# esp32_master_board.net
KiCad netlist of a schematic drawn in EAGLE
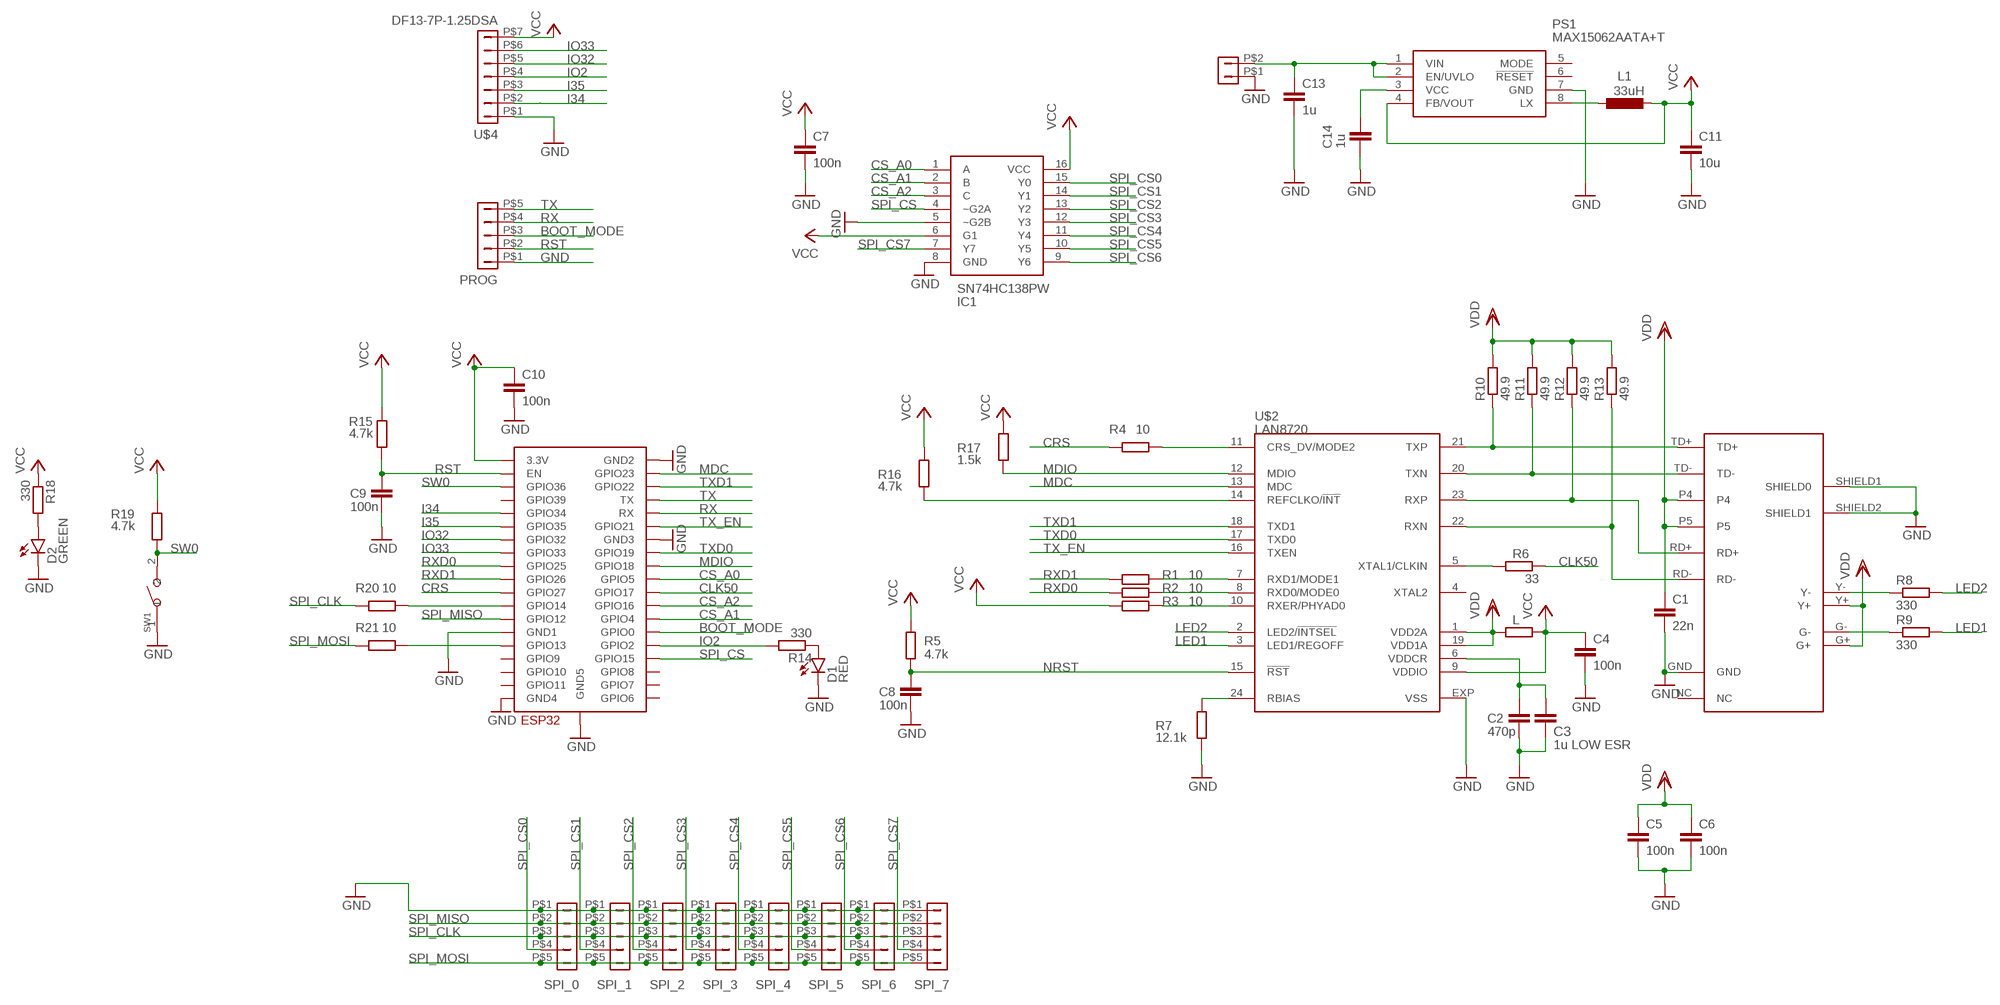
[diagram p0: schematic, sheet 1]

(export (version "E")
  (design (tool "Eeschema 10.0.6"))
  (components
    (comp (ref "C1")
      (value "22n")
      (footprint "eagle-import:C0402")
      (libsource (lib "eagle-import") (part "C-EUC0402"))
    )
    (comp (ref "C2")
      (value "470p")
      (footprint "eagle-import:C0402")
      (libsource (lib "eagle-import") (part "C-EUC0402"))
    )
    (comp (ref "C3")
      (value "1u LOW ESR")
      (footprint "eagle-import:C0402")
      (libsource (lib "eagle-import") (part "C-EUC0402"))
    )
    (comp (ref "C4")
      (value "100n")
      (footprint "eagle-import:C0402")
      (libsource (lib "eagle-import") (part "C-EUC0402"))
    )
    (comp (ref "C5")
      (value "100n")
      (footprint "eagle-import:C0402")
      (libsource (lib "eagle-import") (part "C-EUC0402"))
    )
    (comp (ref "C6")
      (value "100n")
      (footprint "eagle-import:C0402")
      (libsource (lib "eagle-import") (part "C-EUC0402"))
    )
    (comp (ref "C7")
      (value "100n")
      (footprint "eagle-import:C0402")
      (libsource (lib "eagle-import") (part "C-EUC0402"))
    )
    (comp (ref "C8")
      (value "100n")
      (footprint "eagle-import:C0402")
      (libsource (lib "eagle-import") (part "C-EUC0402"))
    )
    (comp (ref "C9")
      (value "100n")
      (footprint "eagle-import:C0402")
      (libsource (lib "eagle-import") (part "C-EUC0402"))
    )
    (comp (ref "C10")
      (value "100n")
      (footprint "eagle-import:C0805K")
      (libsource (lib "eagle-import") (part "C-EUC0805K"))
    )
    (comp (ref "C11")
      (value "10u")
      (footprint "eagle-import:C0805K")
      (libsource (lib "eagle-import") (part "C-EUC0805K"))
    )
    (comp (ref "C13")
      (value "1u")
      (footprint "eagle-import:C0805K")
      (libsource (lib "eagle-import") (part "C-EUC0805K"))
    )
    (comp (ref "C14")
      (value "1u")
      (footprint "eagle-import:C0402")
      (libsource (lib "eagle-import") (part "C-EUC0402"))
    )
    (comp (ref "D1")
      (value "RED")
      (footprint "eagle-import:CHIPLED_0805")
      (libsource (lib "eagle-import") (part "LEDCHIPLED_0805"))
    )
    (comp (ref "D2")
      (value "GREEN")
      (footprint "eagle-import:CHIPLED_0805")
      (libsource (lib "eagle-import") (part "LEDCHIPLED_0805"))
    )
    (comp (ref "IC1")
      (value "SN74HC138PW")
      (footprint "eagle-import:SOP65P640X120-16N")
      (fields (field (name "RS_PART_NUMBER") "6631928"))
      (libsource (lib "eagle-import") (part "SN74HC138PW"))
    )
    (comp (ref "L")
      (value "R-EU_R0402")
      (footprint "eagle-import:R0402")
      (libsource (lib "eagle-import") (part "R-EU_R0402"))
    )
    (comp (ref "L1")
      (value "33uH")
      (footprint "eagle-import:POWER-CHOKE_WE-TPC")
      (libsource (lib "eagle-import") (part "L-EUWE-TPC"))
    )
    (comp (ref "POWER")
      (value "DF13-2P-1.25DSA")
      (footprint "eagle-import:DF13-2P-1.25DSA")
      (libsource (lib "eagle-import") (part "DF13-2P-1.25DSA"))
    )
    (comp (ref "PROG")
      (value "DF13-5P-1.25DSA")
      (footprint "eagle-import:DF13-5P-1.25DSA")
      (libsource (lib "eagle-import") (part "DF13-5P-1.25DSA"))
    )
    (comp (ref "PS1")
      (value "MAX15062AATA+T")
      (footprint "eagle-import:MAX14591ETAT")
      (fields (field (name "MOUSER_PART_NUMBER") "700-MAX15062AATA+T"))
      (libsource (lib "eagle-import") (part "MAX15062AATA+T"))
    )
    (comp (ref "R1")
      (value "10")
      (footprint "eagle-import:R0402")
      (libsource (lib "eagle-import") (part "R-EU_R0402"))
    )
    (comp (ref "R2")
      (value "10")
      (footprint "eagle-import:R0402")
      (libsource (lib "eagle-import") (part "R-EU_R0402"))
    )
    (comp (ref "R3")
      (value "10")
      (footprint "eagle-import:R0402")
      (libsource (lib "eagle-import") (part "R-EU_R0402"))
    )
    (comp (ref "R4")
      (value "10")
      (footprint "eagle-import:R0402")
      (libsource (lib "eagle-import") (part "R-EU_R0402"))
    )
    (comp (ref "R5")
      (value "4.7k")
      (footprint "eagle-import:R0402")
      (libsource (lib "eagle-import") (part "R-EU_R0402"))
    )
    (comp (ref "R6")
      (value "33")
      (footprint "eagle-import:R0402")
      (libsource (lib "eagle-import") (part "R-EU_R0402"))
    )
    (comp (ref "R7")
      (value "12.1k")
      (footprint "eagle-import:R0402")
      (libsource (lib "eagle-import") (part "R-EU_R0402"))
    )
    (comp (ref "R8")
      (value "330")
      (footprint "eagle-import:R0402")
      (libsource (lib "eagle-import") (part "R-EU_R0402"))
    )
    (comp (ref "R9")
      (value "330")
      (footprint "eagle-import:R0402")
      (libsource (lib "eagle-import") (part "R-EU_R0402"))
    )
    (comp (ref "R10")
      (value "49.9")
      (footprint "eagle-import:R0402")
      (libsource (lib "eagle-import") (part "R-EU_R0402"))
    )
    (comp (ref "R11")
      (value "49.9")
      (footprint "eagle-import:R0402")
      (libsource (lib "eagle-import") (part "R-EU_R0402"))
    )
    (comp (ref "R12")
      (value "49.9")
      (footprint "eagle-import:R0402")
      (libsource (lib "eagle-import") (part "R-EU_R0402"))
    )
    (comp (ref "R13")
      (value "49.9")
      (footprint "eagle-import:R0402")
      (libsource (lib "eagle-import") (part "R-EU_R0402"))
    )
    (comp (ref "R14")
      (value "330")
      (footprint "eagle-import:R0402")
      (libsource (lib "eagle-import") (part "R-EU_R0402"))
    )
    (comp (ref "R15")
      (value "4.7k")
      (footprint "eagle-import:R0402")
      (libsource (lib "eagle-import") (part "R-EU_R0402"))
    )
    (comp (ref "R16")
      (value "4.7k")
      (footprint "eagle-import:R0402")
      (libsource (lib "eagle-import") (part "R-EU_R0402"))
    )
    (comp (ref "R17")
      (value "1.5k")
      (footprint "eagle-import:R0402")
      (libsource (lib "eagle-import") (part "R-EU_R0402"))
    )
    (comp (ref "R18")
      (value "330")
      (footprint "eagle-import:R0402")
      (libsource (lib "eagle-import") (part "R-EU_R0402"))
    )
    (comp (ref "R19")
      (value "4.7k")
      (footprint "eagle-import:R0402")
      (libsource (lib "eagle-import") (part "R-EU_R0402"))
    )
    (comp (ref "R20")
      (value "10")
      (footprint "eagle-import:R0402")
      (libsource (lib "eagle-import") (part "R-EU_R0402"))
    )
    (comp (ref "R21")
      (value "10")
      (footprint "eagle-import:R0402")
      (libsource (lib "eagle-import") (part "R-EU_R0402"))
    )
    (comp (ref "SPI_0")
      (value "DF13-5P-1.25DSA")
      (footprint "eagle-import:DF13-5P-1.25DSA")
      (libsource (lib "eagle-import") (part "DF13-5P-1.25DSA"))
    )
    (comp (ref "SPI_1")
      (value "DF13-5P-1.25DSA")
      (footprint "eagle-import:DF13-5P-1.25DSA")
      (libsource (lib "eagle-import") (part "DF13-5P-1.25DSA"))
    )
    (comp (ref "SPI_2")
      (value "DF13-5P-1.25DSA")
      (footprint "eagle-import:DF13-5P-1.25DSA")
      (libsource (lib "eagle-import") (part "DF13-5P-1.25DSA"))
    )
    (comp (ref "SPI_3")
      (value "DF13-5P-1.25DSA")
      (footprint "eagle-import:DF13-5P-1.25DSA")
      (libsource (lib "eagle-import") (part "DF13-5P-1.25DSA"))
    )
    (comp (ref "SPI_4")
      (value "DF13-5P-1.25DSA")
      (footprint "eagle-import:DF13-5P-1.25DSA")
      (libsource (lib "eagle-import") (part "DF13-5P-1.25DSA"))
    )
    (comp (ref "SPI_5")
      (value "DF13-5P-1.25DSA")
      (footprint "eagle-import:DF13-5P-1.25DSA")
      (libsource (lib "eagle-import") (part "DF13-5P-1.25DSA"))
    )
    (comp (ref "SPI_6")
      (value "DF13-5P-1.25DSA")
      (footprint "eagle-import:DF13-5P-1.25DSA")
      (libsource (lib "eagle-import") (part "DF13-5P-1.25DSA"))
    )
    (comp (ref "SPI_7")
      (value "DF13-5P-1.25DSA")
      (footprint "eagle-import:DF13-5P-1.25DSA")
      (libsource (lib "eagle-import") (part "DF13-5P-1.25DSA"))
    )
    (comp (ref "SW1")
      (value "B3U-1000P-2P-SMD")
      (footprint "eagle-import:SW2-2.6-3.0X2.5X1.2+0.4MM")
      (libsource (lib "eagle-import") (part "SMD-BUTTON(2P-3.0X2.5X1.2+0.4MM)-B3U-1000P-2P-SMD"))
    )
    (comp (ref "U$1")
      (value "ESP32-WROOM")
      (footprint "eagle-import:ESP32-WROOM")
      (libsource (lib "eagle-import") (part "ESP32-WROOM"))
    )
    (comp (ref "U$2")
      (value "LAN8720")
      (footprint "eagle-import:QFN24")
      (libsource (lib "eagle-import") (part "LAN8720"))
    )
    (comp (ref "U$3")
      (value "HR911105A")
      (footprint "eagle-import:RJ45")
      (libsource (lib "eagle-import") (part "HR911105A"))
    )
    (comp (ref "U$4")
      (value "DF13-7P-1.25DSA")
      (footprint "eagle-import:DF13-7P-1.25DSA")
      (libsource (lib "eagle-import") (part "DF13-7P-1.25DSA"))
    )
  )
  (nets
    (net (code "1") (name "/BOOT_MODE") (class "Default")
      (node (ref "PROG") (pin "P$3") (pinfunction "3_P$3") (pintype "passive"))
      (node (ref "U$1") (pin "IO0") (pinfunction "GPIO0_IO0") (pintype "bidirectional"))
    )
    (net (code "2") (name "/CLK50") (class "Default")
      (node (ref "R6") (pin "1") (pinfunction "1_1") (pintype "passive"))
      (node (ref "U$1") (pin "IO17") (pinfunction "GPIO17_IO17") (pintype "bidirectional"))
    )
    (net (code "3") (name "/CRS") (class "Default")
      (node (ref "R4") (pin "1") (pinfunction "1_1") (pintype "passive"))
      (node (ref "U$1") (pin "IO27") (pinfunction "GPIO27_IO27") (pintype "bidirectional"))
    )
    (net (code "4") (name "/CS_A0") (class "Default")
      (node (ref "IC1") (pin "1") (pinfunction "A_1") (pintype "bidirectional"))
      (node (ref "U$1") (pin "IO5") (pinfunction "GPIO5_IO5") (pintype "bidirectional"))
    )
    (net (code "5") (name "/CS_A1") (class "Default")
      (node (ref "IC1") (pin "2") (pinfunction "B_2") (pintype "bidirectional"))
      (node (ref "U$1") (pin "IO4") (pinfunction "GPIO4_IO4") (pintype "bidirectional"))
    )
    (net (code "6") (name "/CS_A2") (class "Default")
      (node (ref "IC1") (pin "3") (pinfunction "C_3") (pintype "bidirectional"))
      (node (ref "U$1") (pin "IO16") (pinfunction "GPIO16_IO16") (pintype "bidirectional"))
    )
    (net (code "7") (name "/I34") (class "Default")
      (node (ref "U$1") (pin "IO34") (pinfunction "GPIO34_IO34") (pintype "bidirectional"))
      (node (ref "U$4") (pin "P$2") (pinfunction "2_P$2") (pintype "passive"))
    )
    (net (code "8") (name "/I35") (class "Default")
      (node (ref "U$1") (pin "IO35") (pinfunction "GPIO35_IO35") (pintype "bidirectional"))
      (node (ref "U$4") (pin "P$3") (pinfunction "3_P$3") (pintype "passive"))
    )
    (net (code "9") (name "/IO2") (class "Default")
      (node (ref "R14") (pin "2") (pinfunction "2_2") (pintype "passive"))
      (node (ref "U$1") (pin "IO2") (pinfunction "GPIO2_IO2") (pintype "bidirectional"))
      (node (ref "U$4") (pin "P$4") (pinfunction "4_P$4") (pintype "passive"))
    )
    (net (code "10") (name "/IO32") (class "Default")
      (node (ref "U$1") (pin "IO32") (pinfunction "GPIO32_IO32") (pintype "bidirectional"))
      (node (ref "U$4") (pin "P$5") (pinfunction "5_P$5") (pintype "passive"))
    )
    (net (code "11") (name "/IO33") (class "Default")
      (node (ref "U$1") (pin "IO33") (pinfunction "GPIO33_IO33") (pintype "bidirectional"))
      (node (ref "U$4") (pin "P$6") (pinfunction "6_P$6") (pintype "passive"))
    )
    (net (code "12") (name "/LED1") (class "Default")
      (node (ref "R9") (pin "2") (pinfunction "2_2") (pintype "passive"))
      (node (ref "U$2") (pin "3") (pinfunction "LED1/REGOFF_3") (pintype "bidirectional"))
    )
    (net (code "13") (name "/LED2") (class "Default")
      (node (ref "R8") (pin "2") (pinfunction "2_2") (pintype "passive"))
      (node (ref "U$2") (pin "2") (pinfunction "LED2/~{INTSEL}_2") (pintype "bidirectional"))
    )
    (net (code "14") (name "/MDC") (class "Default")
      (node (ref "U$1") (pin "IO23") (pinfunction "GPIO23_IO23") (pintype "bidirectional"))
      (node (ref "U$2") (pin "13") (pinfunction "MDC_13") (pintype "bidirectional"))
    )
    (net (code "15") (name "/MDIO") (class "Default")
      (node (ref "R17") (pin "1") (pinfunction "1_1") (pintype "passive"))
      (node (ref "U$1") (pin "IO18") (pinfunction "GPIO18_IO18") (pintype "bidirectional"))
      (node (ref "U$2") (pin "12") (pinfunction "MDIO_12") (pintype "bidirectional"))
    )
    (net (code "16") (name "/NRST") (class "Default")
      (node (ref "C8") (pin "1") (pinfunction "1_1") (pintype "passive"))
      (node (ref "R5") (pin "1") (pinfunction "1_1") (pintype "passive"))
      (node (ref "U$2") (pin "15") (pinfunction "~{RST}_15") (pintype "bidirectional"))
    )
    (net (code "17") (name "/RST") (class "Default")
      (node (ref "C9") (pin "1") (pinfunction "1_1") (pintype "passive"))
      (node (ref "PROG") (pin "P$2") (pinfunction "2_P$2") (pintype "passive"))
      (node (ref "R15") (pin "1") (pinfunction "1_1") (pintype "passive"))
      (node (ref "U$1") (pin "EN") (pinfunction "EN_EN") (pintype "bidirectional"))
    )
    (net (code "18") (name "/RX") (class "Default")
      (node (ref "PROG") (pin "P$4") (pinfunction "4_P$4") (pintype "passive"))
      (node (ref "U$1") (pin "RX") (pinfunction "RX_RX") (pintype "bidirectional"))
    )
    (net (code "19") (name "/RXD0") (class "Default")
      (node (ref "R2") (pin "1") (pinfunction "1_1") (pintype "passive"))
      (node (ref "U$1") (pin "IO25") (pinfunction "GPIO25_IO25") (pintype "bidirectional"))
    )
    (net (code "20") (name "/RXD1") (class "Default")
      (node (ref "R1") (pin "1") (pinfunction "1_1") (pintype "passive"))
      (node (ref "U$1") (pin "IO26") (pinfunction "GPIO26_IO26") (pintype "bidirectional"))
    )
    (net (code "21") (name "/SPI_CLK") (class "Default")
      (node (ref "R20") (pin "1") (pinfunction "1_1") (pintype "passive"))
      (node (ref "SPI_0") (pin "P$3") (pinfunction "3_P$3") (pintype "passive"))
      (node (ref "SPI_1") (pin "P$3") (pinfunction "3_P$3") (pintype "passive"))
      (node (ref "SPI_2") (pin "P$3") (pinfunction "3_P$3") (pintype "passive"))
      (node (ref "SPI_3") (pin "P$3") (pinfunction "3_P$3") (pintype "passive"))
      (node (ref "SPI_4") (pin "P$3") (pinfunction "3_P$3") (pintype "passive"))
      (node (ref "SPI_5") (pin "P$3") (pinfunction "3_P$3") (pintype "passive"))
      (node (ref "SPI_6") (pin "P$3") (pinfunction "3_P$3") (pintype "passive"))
      (node (ref "SPI_7") (pin "P$3") (pinfunction "3_P$3") (pintype "passive"))
    )
    (net (code "22") (name "/SPI_CS") (class "Default")
      (node (ref "IC1") (pin "4") (pinfunction "~{G2A}_4") (pintype "bidirectional"))
      (node (ref "U$1") (pin "IO15") (pinfunction "GPIO15_IO15") (pintype "bidirectional"))
    )
    (net (code "23") (name "/SPI_CS0") (class "Default")
      (node (ref "IC1") (pin "15") (pinfunction "Y0_15") (pintype "bidirectional"))
      (node (ref "SPI_0") (pin "P$4") (pinfunction "4_P$4") (pintype "passive"))
    )
    (net (code "24") (name "/SPI_CS1") (class "Default")
      (node (ref "IC1") (pin "14") (pinfunction "Y1_14") (pintype "bidirectional"))
      (node (ref "SPI_1") (pin "P$4") (pinfunction "4_P$4") (pintype "passive"))
    )
    (net (code "25") (name "/SPI_CS2") (class "Default")
      (node (ref "IC1") (pin "13") (pinfunction "Y2_13") (pintype "bidirectional"))
      (node (ref "SPI_2") (pin "P$4") (pinfunction "4_P$4") (pintype "passive"))
    )
    (net (code "26") (name "/SPI_CS3") (class "Default")
      (node (ref "IC1") (pin "12") (pinfunction "Y3_12") (pintype "bidirectional"))
      (node (ref "SPI_3") (pin "P$4") (pinfunction "4_P$4") (pintype "passive"))
    )
    (net (code "27") (name "/SPI_CS4") (class "Default")
      (node (ref "IC1") (pin "11") (pinfunction "Y4_11") (pintype "bidirectional"))
      (node (ref "SPI_4") (pin "P$4") (pinfunction "4_P$4") (pintype "passive"))
    )
    (net (code "28") (name "/SPI_CS5") (class "Default")
      (node (ref "IC1") (pin "10") (pinfunction "Y5_10") (pintype "bidirectional"))
      (node (ref "SPI_5") (pin "P$4") (pinfunction "4_P$4") (pintype "passive"))
    )
    (net (code "29") (name "/SPI_CS6") (class "Default")
      (node (ref "IC1") (pin "9") (pinfunction "Y6_9") (pintype "bidirectional"))
      (node (ref "SPI_6") (pin "P$4") (pinfunction "4_P$4") (pintype "passive"))
    )
    (net (code "30") (name "/SPI_CS7") (class "Default")
      (node (ref "IC1") (pin "7") (pinfunction "Y7_7") (pintype "bidirectional"))
      (node (ref "SPI_7") (pin "P$4") (pinfunction "4_P$4") (pintype "passive"))
    )
    (net (code "31") (name "/SPI_MISO") (class "Default")
      (node (ref "SPI_0") (pin "P$2") (pinfunction "2_P$2") (pintype "passive"))
      (node (ref "SPI_1") (pin "P$2") (pinfunction "2_P$2") (pintype "passive"))
      (node (ref "SPI_2") (pin "P$2") (pinfunction "2_P$2") (pintype "passive"))
      (node (ref "SPI_3") (pin "P$2") (pinfunction "2_P$2") (pintype "passive"))
      (node (ref "SPI_4") (pin "P$2") (pinfunction "2_P$2") (pintype "passive"))
      (node (ref "SPI_5") (pin "P$2") (pinfunction "2_P$2") (pintype "passive"))
      (node (ref "SPI_6") (pin "P$2") (pinfunction "2_P$2") (pintype "passive"))
      (node (ref "SPI_7") (pin "P$2") (pinfunction "2_P$2") (pintype "passive"))
      (node (ref "U$1") (pin "IO12") (pinfunction "GPIO12_IO12") (pintype "bidirectional"))
    )
    (net (code "32") (name "/SPI_MOSI") (class "Default")
      (node (ref "R21") (pin "1") (pinfunction "1_1") (pintype "passive"))
      (node (ref "SPI_0") (pin "P$5") (pinfunction "5_P$5") (pintype "passive"))
      (node (ref "SPI_1") (pin "P$5") (pinfunction "5_P$5") (pintype "passive"))
      (node (ref "SPI_2") (pin "P$5") (pinfunction "5_P$5") (pintype "passive"))
      (node (ref "SPI_3") (pin "P$5") (pinfunction "5_P$5") (pintype "passive"))
      (node (ref "SPI_4") (pin "P$5") (pinfunction "5_P$5") (pintype "passive"))
      (node (ref "SPI_5") (pin "P$5") (pinfunction "5_P$5") (pintype "passive"))
      (node (ref "SPI_6") (pin "P$5") (pinfunction "5_P$5") (pintype "passive"))
      (node (ref "SPI_7") (pin "P$5") (pinfunction "5_P$5") (pintype "passive"))
    )
    (net (code "33") (name "/SW0") (class "Default")
      (node (ref "R19") (pin "1") (pinfunction "1_1") (pintype "passive"))
      (node (ref "SW1") (pin "2") (pinfunction "2_2") (pintype "bidirectional"))
      (node (ref "U$1") (pin "SENSOR_VP") (pinfunction "GPIO36_SENSOR_VP") (pintype "bidirectional"))
    )
    (net (code "34") (name "/TX") (class "Default")
      (node (ref "PROG") (pin "P$5") (pinfunction "5_P$5") (pintype "passive"))
      (node (ref "U$1") (pin "TX") (pinfunction "TX_TX") (pintype "bidirectional"))
    )
    (net (code "35") (name "/TXD0") (class "Default")
      (node (ref "U$1") (pin "IO19") (pinfunction "GPIO19_IO19") (pintype "bidirectional"))
      (node (ref "U$2") (pin "17") (pinfunction "TXD0_17") (pintype "bidirectional"))
    )
    (net (code "36") (name "/TXD1") (class "Default")
      (node (ref "U$1") (pin "IO22") (pinfunction "GPIO22_IO22") (pintype "bidirectional"))
      (node (ref "U$2") (pin "18") (pinfunction "TXD1_18") (pintype "bidirectional"))
    )
    (net (code "37") (name "/TX_EN") (class "Default")
      (node (ref "U$1") (pin "IO21") (pinfunction "GPIO21_IO21") (pintype "bidirectional"))
      (node (ref "U$2") (pin "16") (pinfunction "TXEN_16") (pintype "bidirectional"))
    )
    (net (code "38") (name "GND") (class "Default")
      (node (ref "C1") (pin "2") (pinfunction "2_2") (pintype "passive"))
      (node (ref "C10") (pin "2") (pinfunction "2_2") (pintype "passive"))
      (node (ref "C11") (pin "2") (pinfunction "2_2") (pintype "passive"))
      (node (ref "C13") (pin "2") (pinfunction "2_2") (pintype "passive"))
      (node (ref "C14") (pin "1") (pinfunction "1_1") (pintype "passive"))
      (node (ref "C2") (pin "2") (pinfunction "2_2") (pintype "passive"))
      (node (ref "C3") (pin "2") (pinfunction "2_2") (pintype "passive"))
      (node (ref "C4") (pin "2") (pinfunction "2_2") (pintype "passive"))
      (node (ref "C5") (pin "2") (pinfunction "2_2") (pintype "passive"))
      (node (ref "C6") (pin "2") (pinfunction "2_2") (pintype "passive"))
      (node (ref "C7") (pin "2") (pinfunction "2_2") (pintype "passive"))
      (node (ref "C8") (pin "2") (pinfunction "2_2") (pintype "passive"))
      (node (ref "C9") (pin "2") (pinfunction "2_2") (pintype "passive"))
      (node (ref "D1") (pin "C") (pinfunction "C_C") (pintype "passive"))
      (node (ref "D2") (pin "C") (pinfunction "C_C") (pintype "passive"))
      (node (ref "IC1") (pin "5") (pinfunction "~{G2B}_5") (pintype "bidirectional"))
      (node (ref "IC1") (pin "8") (pinfunction "GND_8") (pintype "bidirectional"))
      (node (ref "POWER") (pin "P$1") (pinfunction "1_P$1") (pintype "passive"))
      (node (ref "PROG") (pin "P$1") (pinfunction "1_P$1") (pintype "passive"))
      (node (ref "PS1") (pin "7") (pinfunction "GND_7") (pintype "bidirectional"))
      (node (ref "R7") (pin "1") (pinfunction "1_1") (pintype "passive"))
      (node (ref "SPI_0") (pin "P$1") (pinfunction "1_P$1") (pintype "passive"))
      (node (ref "SPI_1") (pin "P$1") (pinfunction "1_P$1") (pintype "passive"))
      (node (ref "SPI_2") (pin "P$1") (pinfunction "1_P$1") (pintype "passive"))
      (node (ref "SPI_3") (pin "P$1") (pinfunction "1_P$1") (pintype "passive"))
      (node (ref "SPI_4") (pin "P$1") (pinfunction "1_P$1") (pintype "passive"))
      (node (ref "SPI_5") (pin "P$1") (pinfunction "1_P$1") (pintype "passive"))
      (node (ref "SPI_6") (pin "P$1") (pinfunction "1_P$1") (pintype "passive"))
      (node (ref "SPI_7") (pin "P$1") (pinfunction "1_P$1") (pintype "passive"))
      (node (ref "SW1") (pin "1") (pinfunction "1_1") (pintype "bidirectional"))
      (node (ref "U$1") (pin "GND1") (pinfunction "GND1_GND1") (pintype "bidirectional"))
      (node (ref "U$1") (pin "GND2") (pinfunction "GND2_GND2") (pintype "bidirectional"))
      (node (ref "U$1") (pin "GND3") (pinfunction "GND3_GND3") (pintype "bidirectional"))
      (node (ref "U$1") (pin "GND4") (pinfunction "GND4_GND4") (pintype "bidirectional"))
      (node (ref "U$1") (pin "GND5") (pinfunction "GND5_GND5") (pintype "bidirectional"))
      (node (ref "U$2") (pin "EXP") (pinfunction "VSS_EXP") (pintype "power_in"))
      (node (ref "U$3") (pin "GND") (pinfunction "GND_GND") (pintype "bidirectional"))
      (node (ref "U$3") (pin "SHIELD1") (pinfunction "SHIELD0_SHIELD1") (pintype "bidirectional"))
      (node (ref "U$3") (pin "SHIELD2") (pinfunction "SHIELD1_SHIELD2") (pintype "bidirectional"))
      (node (ref "U$4") (pin "P$1") (pinfunction "1_P$1") (pintype "passive"))
    )
    (net (code "39") (name "Net-(D1-PadA)") (class "Default")
      (node (ref "D1") (pin "A") (pinfunction "A_A") (pintype "passive"))
      (node (ref "R14") (pin "1") (pinfunction "1_1") (pintype "passive"))
    )
    (net (code "40") (name "Net-(D2-PadA)") (class "Default")
      (node (ref "D2") (pin "A") (pinfunction "A_A") (pintype "passive"))
      (node (ref "R18") (pin "2") (pinfunction "2_2") (pintype "passive"))
    )
    (net (code "41") (name "Net-(POWER-2)") (class "Default")
      (node (ref "C13") (pin "1") (pinfunction "1_1") (pintype "passive"))
      (node (ref "POWER") (pin "P$2") (pinfunction "2_P$2") (pintype "passive"))
      (node (ref "PS1") (pin "1") (pinfunction "VIN_1") (pintype "bidirectional"))
      (node (ref "PS1") (pin "2") (pinfunction "EN/UVLO_2") (pintype "bidirectional"))
    )
    (net (code "42") (name "Net-(PS1-LX)") (class "Default")
      (node (ref "L1") (pin "1") (pinfunction "1_1") (pintype "passive"))
      (node (ref "PS1") (pin "8") (pinfunction "LX_8") (pintype "bidirectional"))
    )
    (net (code "43") (name "Net-(PS1-VCC)") (class "Default")
      (node (ref "C14") (pin "2") (pinfunction "2_2") (pintype "passive"))
      (node (ref "PS1") (pin "3") (pinfunction "VCC_3") (pintype "bidirectional"))
    )
    (net (code "44") (name "Net-(R8-Pad1)") (class "Default")
      (node (ref "R8") (pin "1") (pinfunction "1_1") (pintype "passive"))
      (node (ref "U$3") (pin "Y-") (pinfunction "Y-_Y-") (pintype "bidirectional"))
    )
    (net (code "45") (name "Net-(R9-Pad1)") (class "Default")
      (node (ref "R9") (pin "1") (pinfunction "1_1") (pintype "passive"))
      (node (ref "U$3") (pin "G-") (pinfunction "G-_G-") (pintype "bidirectional"))
    )
    (net (code "46") (name "Net-(U$1-GPIO13)") (class "Default")
      (node (ref "R21") (pin "2") (pinfunction "2_2") (pintype "passive"))
      (node (ref "U$1") (pin "IO13") (pinfunction "GPIO13_IO13") (pintype "bidirectional"))
    )
    (net (code "47") (name "Net-(U$1-GPIO14)") (class "Default")
      (node (ref "R20") (pin "2") (pinfunction "2_2") (pintype "passive"))
      (node (ref "U$1") (pin "IO14") (pinfunction "GPIO14_IO14") (pintype "bidirectional"))
    )
    (net (code "48") (name "Net-(U$2-CRS_DV{slash}MODE2)") (class "Default")
      (node (ref "R4") (pin "2") (pinfunction "2_2") (pintype "passive"))
      (node (ref "U$2") (pin "11") (pinfunction "CRS_DV/MODE2_11") (pintype "bidirectional"))
    )
    (net (code "49") (name "Net-(U$2-RBIAS)") (class "Default")
      (node (ref "R7") (pin "2") (pinfunction "2_2") (pintype "passive"))
      (node (ref "U$2") (pin "24") (pinfunction "RBIAS_24") (pintype "bidirectional"))
    )
    (net (code "50") (name "Net-(U$2-REFCLKO{slash}~{INT})") (class "Default")
      (node (ref "R16") (pin "1") (pinfunction "1_1") (pintype "passive"))
      (node (ref "U$2") (pin "14") (pinfunction "REFCLKO/~{INT}_14") (pintype "bidirectional"))
    )
    (net (code "51") (name "Net-(U$2-RXD0{slash}MODE0)") (class "Default")
      (node (ref "R2") (pin "2") (pinfunction "2_2") (pintype "passive"))
      (node (ref "U$2") (pin "8") (pinfunction "RXD0/MODE0_8") (pintype "bidirectional"))
    )
    (net (code "52") (name "Net-(U$2-RXD1{slash}MODE1)") (class "Default")
      (node (ref "R1") (pin "2") (pinfunction "2_2") (pintype "passive"))
      (node (ref "U$2") (pin "7") (pinfunction "RXD1/MODE1_7") (pintype "bidirectional"))
    )
    (net (code "53") (name "Net-(U$2-RXER{slash}PHYAD0)") (class "Default")
      (node (ref "R3") (pin "2") (pinfunction "2_2") (pintype "passive"))
      (node (ref "U$2") (pin "10") (pinfunction "RXER/PHYAD0_10") (pintype "bidirectional"))
    )
    (net (code "54") (name "Net-(U$2-RXN)") (class "Default")
      (node (ref "R13") (pin "1") (pinfunction "1_1") (pintype "passive"))
      (node (ref "U$2") (pin "22") (pinfunction "RXN_22") (pintype "bidirectional"))
      (node (ref "U$3") (pin "RD-") (pinfunction "RD-_RD-") (pintype "bidirectional"))
    )
    (net (code "55") (name "Net-(U$2-RXP)") (class "Default")
      (node (ref "R12") (pin "1") (pinfunction "1_1") (pintype "passive"))
      (node (ref "U$2") (pin "23") (pinfunction "RXP_23") (pintype "bidirectional"))
      (node (ref "U$3") (pin "RD+") (pinfunction "RD+_RD+") (pintype "bidirectional"))
    )
    (net (code "56") (name "Net-(U$2-TXN)") (class "Default")
      (node (ref "R11") (pin "1") (pinfunction "1_1") (pintype "passive"))
      (node (ref "U$2") (pin "20") (pinfunction "TXN_20") (pintype "bidirectional"))
      (node (ref "U$3") (pin "TD-") (pinfunction "TD-_TD-") (pintype "bidirectional"))
    )
    (net (code "57") (name "Net-(U$2-TXP)") (class "Default")
      (node (ref "R10") (pin "1") (pinfunction "1_1") (pintype "passive"))
      (node (ref "U$2") (pin "21") (pinfunction "TXP_21") (pintype "bidirectional"))
      (node (ref "U$3") (pin "TD+") (pinfunction "TD+_TD+") (pintype "bidirectional"))
    )
    (net (code "58") (name "Net-(U$2-VDDCR)") (class "Default")
      (node (ref "C2") (pin "1") (pinfunction "1_1") (pintype "passive"))
      (node (ref "C3") (pin "1") (pinfunction "1_1") (pintype "passive"))
      (node (ref "U$2") (pin "6") (pinfunction "VDDCR_6") (pintype "power_in"))
    )
    (net (code "59") (name "Net-(U$2-XTAL1{slash}CLKIN)") (class "Default")
      (node (ref "R6") (pin "2") (pinfunction "2_2") (pintype "passive"))
      (node (ref "U$2") (pin "5") (pinfunction "XTAL1/CLKIN_5") (pintype "bidirectional"))
    )
    (net (code "60") (name "VCC") (class "Default")
      (node (ref "C10") (pin "1") (pinfunction "1_1") (pintype "passive"))
      (node (ref "C11") (pin "1") (pinfunction "1_1") (pintype "passive"))
      (node (ref "C4") (pin "1") (pinfunction "1_1") (pintype "passive"))
      (node (ref "C7") (pin "1") (pinfunction "1_1") (pintype "passive"))
      (node (ref "IC1") (pin "16") (pinfunction "VCC_16") (pintype "bidirectional"))
      (node (ref "IC1") (pin "6") (pinfunction "G1_6") (pintype "bidirectional"))
      (node (ref "L") (pin "1") (pinfunction "1_1") (pintype "passive"))
      (node (ref "L1") (pin "2") (pinfunction "2_2") (pintype "passive"))
      (node (ref "PS1") (pin "4") (pinfunction "FB/VOUT_4") (pintype "bidirectional"))
      (node (ref "R15") (pin "2") (pinfunction "2_2") (pintype "passive"))
      (node (ref "R16") (pin "2") (pinfunction "2_2") (pintype "passive"))
      (node (ref "R17") (pin "2") (pinfunction "2_2") (pintype "passive"))
      (node (ref "R18") (pin "1") (pinfunction "1_1") (pintype "passive"))
      (node (ref "R19") (pin "2") (pinfunction "2_2") (pintype "passive"))
      (node (ref "R3") (pin "1") (pinfunction "1_1") (pintype "passive"))
      (node (ref "R5") (pin "2") (pinfunction "2_2") (pintype "passive"))
      (node (ref "U$1") (pin "3V3") (pinfunction "3.3V_3V3") (pintype "bidirectional"))
      (node (ref "U$2") (pin "9") (pinfunction "VDDIO_9") (pintype "power_in"))
      (node (ref "U$4") (pin "P$7") (pinfunction "7_P$7") (pintype "passive"))
    )
    (net (code "61") (name "VDD") (class "Default")
      (node (ref "C1") (pin "1") (pinfunction "1_1") (pintype "passive"))
      (node (ref "C5") (pin "1") (pinfunction "1_1") (pintype "passive"))
      (node (ref "C6") (pin "1") (pinfunction "1_1") (pintype "passive"))
      (node (ref "L") (pin "2") (pinfunction "2_2") (pintype "passive"))
      (node (ref "R10") (pin "2") (pinfunction "2_2") (pintype "passive"))
      (node (ref "R11") (pin "2") (pinfunction "2_2") (pintype "passive"))
      (node (ref "R12") (pin "2") (pinfunction "2_2") (pintype "passive"))
      (node (ref "R13") (pin "2") (pinfunction "2_2") (pintype "passive"))
      (node (ref "U$2") (pin "1") (pinfunction "VDD2A_1") (pintype "power_in"))
      (node (ref "U$2") (pin "19") (pinfunction "VDD1A_19") (pintype "power_in"))
      (node (ref "U$3") (pin "G+") (pinfunction "G+_G+") (pintype "bidirectional"))
      (node (ref "U$3") (pin "P4") (pinfunction "P4_P4") (pintype "bidirectional"))
      (node (ref "U$3") (pin "P5") (pinfunction "P5_P5") (pintype "bidirectional"))
      (node (ref "U$3") (pin "Y+") (pinfunction "Y+_Y+") (pintype "bidirectional"))
    )
    (net (code "62") (name "unconnected-(PS1-MODE-Pad5)") (class "Default")
      (node (ref "PS1") (pin "5") (pinfunction "MODE_5") (pintype "bidirectional"))
    )
    (net (code "63") (name "unconnected-(PS1-~{RESET}-Pad6)") (class "Default")
      (node (ref "PS1") (pin "6") (pinfunction "~{RESET}_6") (pintype "bidirectional"))
    )
    (net (code "64") (name "unconnected-(U$1-GPIO6-PadCLK)") (class "Default")
      (node (ref "U$1") (pin "CLK") (pinfunction "GPIO6_CLK") (pintype "bidirectional"))
    )
    (net (code "65") (name "unconnected-(U$1-GPIO7-PadSD0)") (class "Default")
      (node (ref "U$1") (pin "SD0") (pinfunction "GPIO7_SD0") (pintype "bidirectional"))
    )
    (net (code "66") (name "unconnected-(U$1-GPIO8-PadSD1)") (class "Default")
      (node (ref "U$1") (pin "SD1") (pinfunction "GPIO8_SD1") (pintype "bidirectional"))
    )
    (net (code "67") (name "unconnected-(U$1-GPIO9-PadSD2)") (class "Default")
      (node (ref "U$1") (pin "SD2") (pinfunction "GPIO9_SD2") (pintype "bidirectional"))
    )
    (net (code "68") (name "unconnected-(U$1-GPIO10-PadSD3)") (class "Default")
      (node (ref "U$1") (pin "SD3") (pinfunction "GPIO10_SD3") (pintype "bidirectional"))
    )
    (net (code "69") (name "unconnected-(U$1-GPIO11-PadCMD)") (class "Default")
      (node (ref "U$1") (pin "CMD") (pinfunction "GPIO11_CMD") (pintype "bidirectional"))
    )
    (net (code "70") (name "unconnected-(U$1-GPIO39-PadSENSOR_VN)") (class "Default")
      (node (ref "U$1") (pin "SENSOR_VN") (pinfunction "GPIO39_SENSOR_VN") (pintype "bidirectional"))
    )
    (net (code "71") (name "unconnected-(U$2-XTAL2-Pad4)") (class "Default")
      (node (ref "U$2") (pin "4") (pinfunction "XTAL2_4") (pintype "bidirectional"))
    )
    (net (code "72") (name "unconnected-(U$3-PadNC)") (class "Default")
      (node (ref "U$3") (pin "NC") (pinfunction "NC_NC") (pintype "bidirectional"))
    )
  )
)
